# Pwr_Brd2.net
KiCad netlist of a schematic drawn in Altium Designer
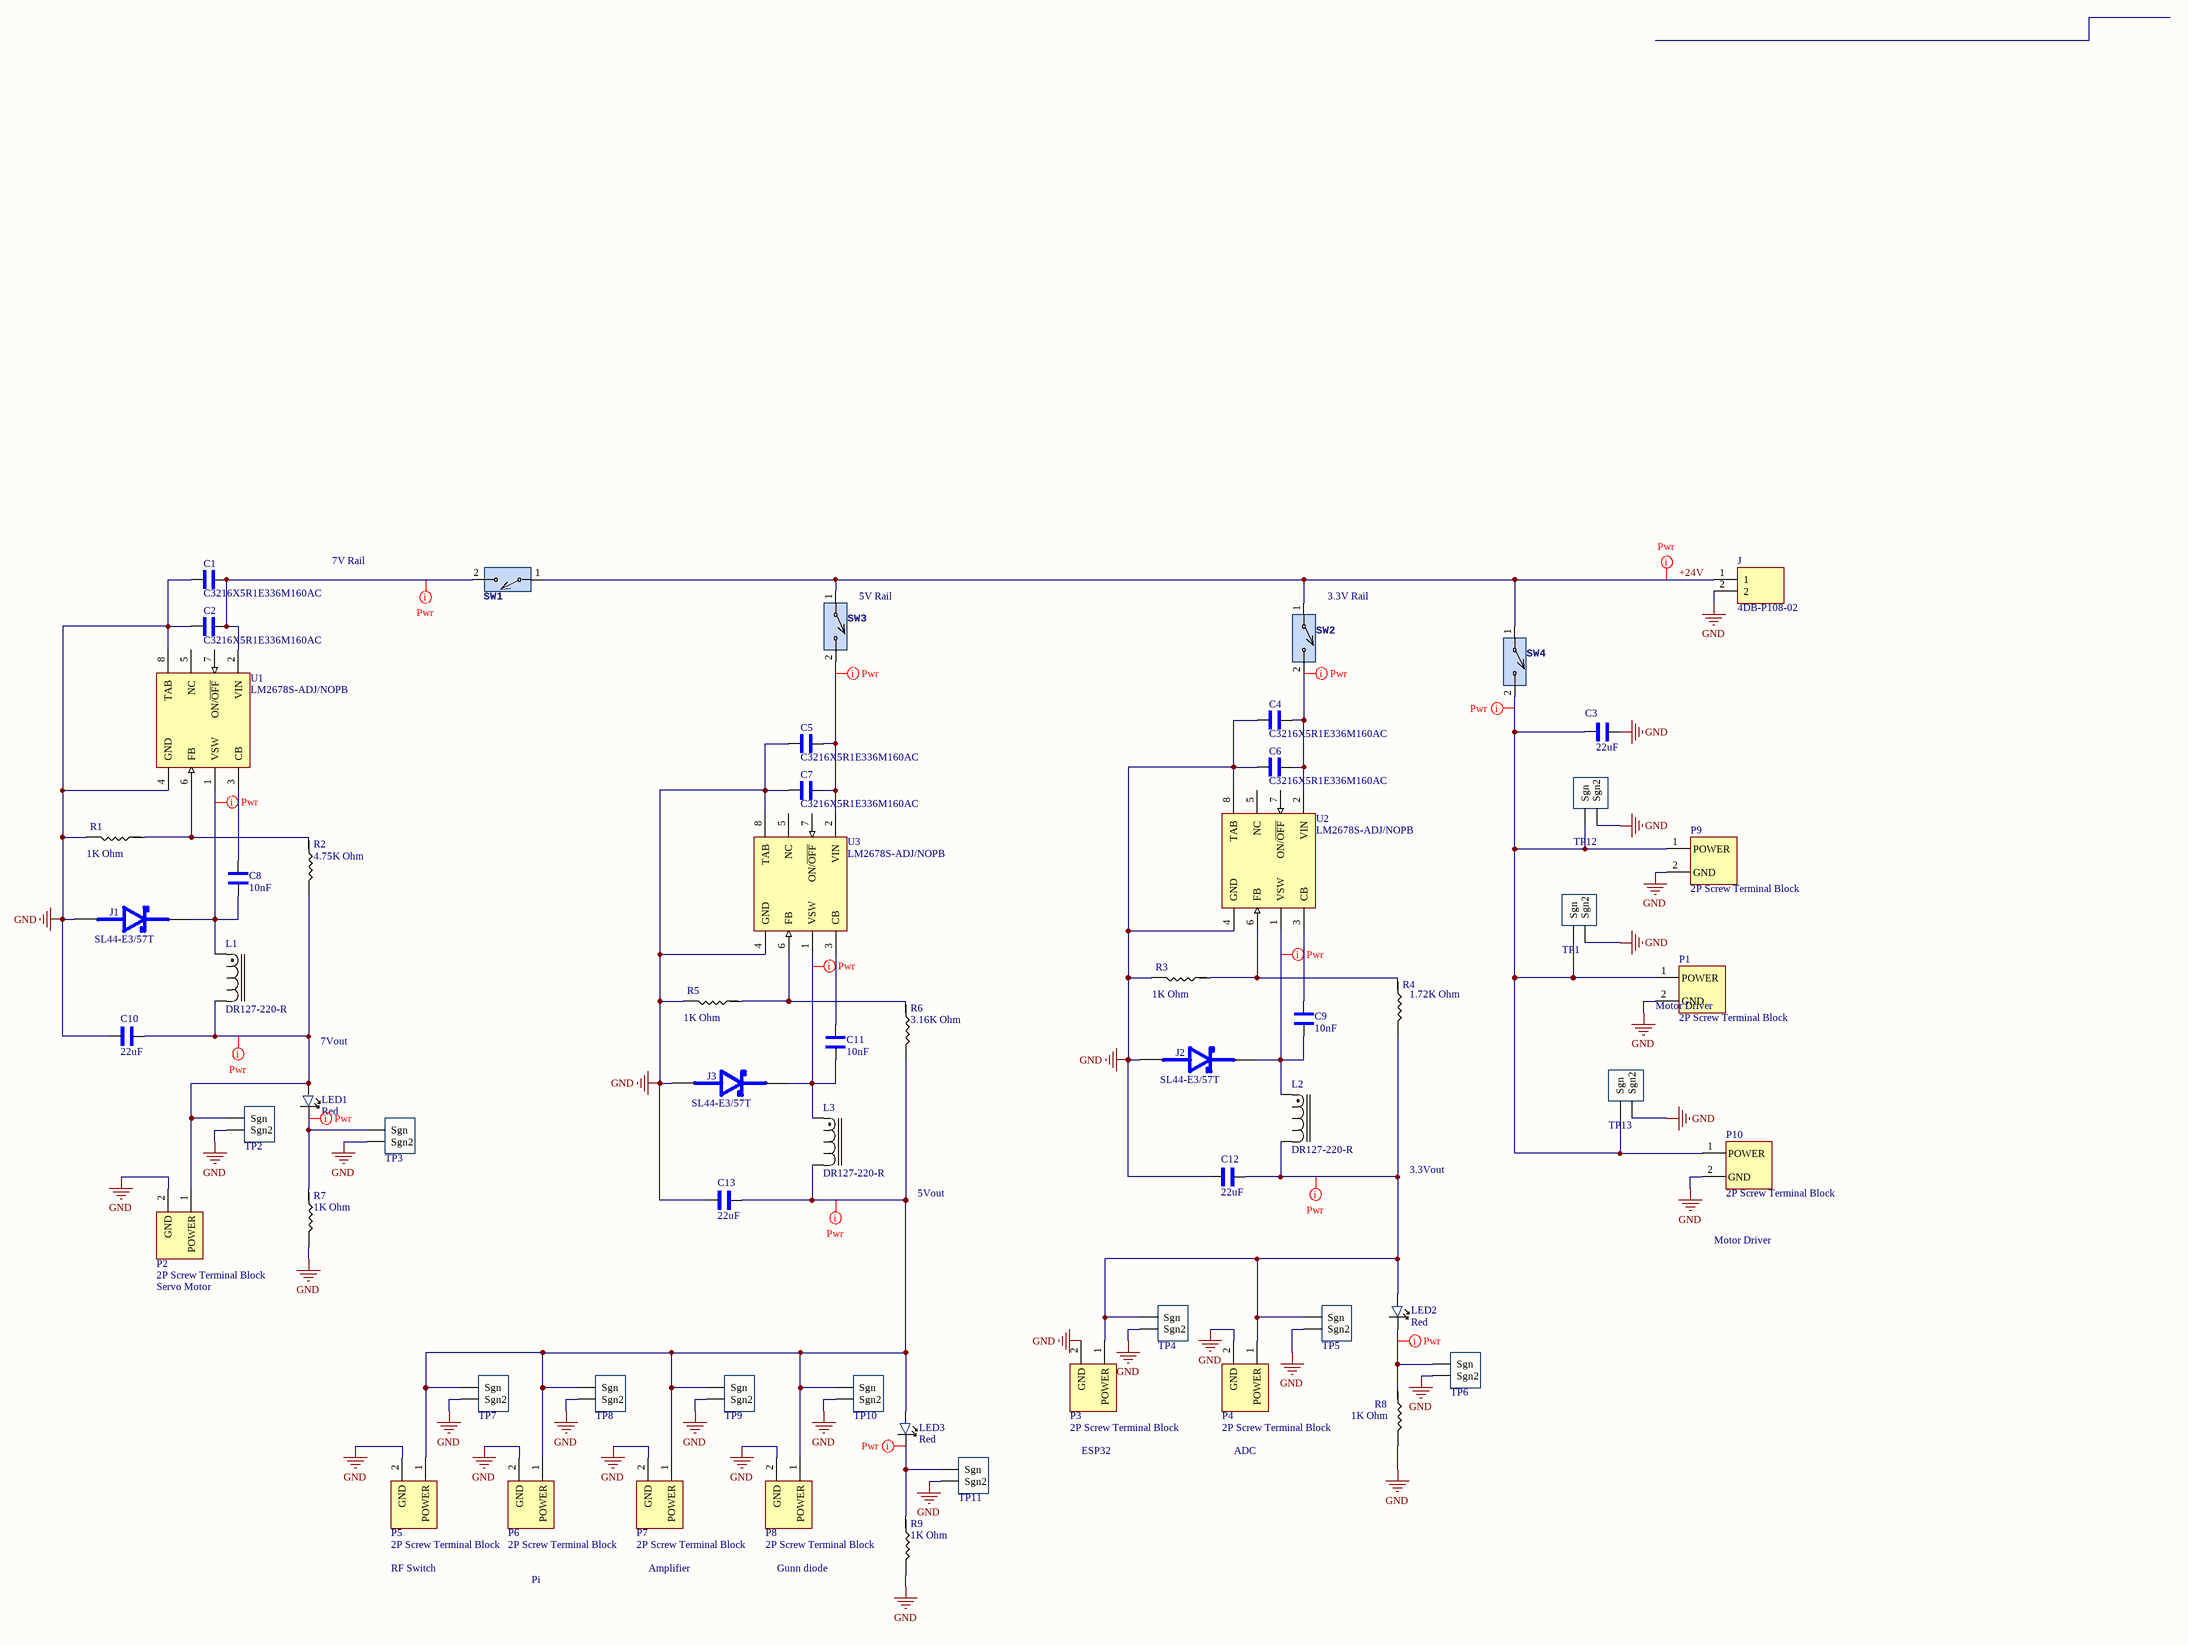
[diagram p0: Pwr_Brd2.SchDoc]

(export (version "E")
  (design (tool "Eeschema 10.0.6"))
  (components
    (comp (ref "C1")
      (value "C3216X5R1E336M160AC")
      (footprint "CAPC3216X180N")
      (description "Cap Ceramic 33uF 25V X5R 20% Pad SMD 1206 85Â°C Low ESR T/R")
      (fields (field (name "MF") "TDK Electronics"))
      (libsource (lib "C3216X5R1E336M160AC") (part "C3216X5R1E336M160AC"))
    )
    (comp (ref "C2")
      (value "C3216X5R1E336M160AC")
      (footprint "CAPC3216X180N")
      (description "Cap Ceramic 33uF 25V X5R 20% Pad SMD 1206 85Â°C Low ESR T/R")
      (fields (field (name "MF") "TDK Electronics"))
      (libsource (lib "C3216X5R1E336M160AC") (part "C3216X5R1E336M160AC"))
    )
    (comp (ref "C3")
      (value "22uF")
      (footprint "1206_Passive_Capacitor")
      (description "22uF ±10% 25V X5R 1206 Multilayer Ceramic Capacitors MLCC - SMD/SMT RoHS")
      (fields (field (name "MFR PART #") "CL31A226KAHNNNE") (field (name "LCSC PART#") "C12891"))
      (libsource (lib "Capstone_Stock_Library") (part "C_22uF_1206"))
    )
    (comp (ref "C4")
      (value "C3216X5R1E336M160AC")
      (footprint "CAPC3216X180N")
      (description "Cap Ceramic 33uF 25V X5R 20% Pad SMD 1206 85Â°C Low ESR T/R")
      (fields (field (name "MF") "TDK Electronics"))
      (libsource (lib "C3216X5R1E336M160AC") (part "C3216X5R1E336M160AC"))
    )
    (comp (ref "C5")
      (value "C3216X5R1E336M160AC")
      (footprint "CAPC3216X180N")
      (description "Cap Ceramic 33uF 25V X5R 20% Pad SMD 1206 85Â°C Low ESR T/R")
      (fields (field (name "MF") "TDK Electronics"))
      (libsource (lib "C3216X5R1E336M160AC") (part "C3216X5R1E336M160AC"))
    )
    (comp (ref "C6")
      (value "C3216X5R1E336M160AC")
      (footprint "CAPC3216X180N")
      (description "Cap Ceramic 33uF 25V X5R 20% Pad SMD 1206 85Â°C Low ESR T/R")
      (fields (field (name "MF") "TDK Electronics"))
      (libsource (lib "C3216X5R1E336M160AC") (part "C3216X5R1E336M160AC"))
    )
    (comp (ref "C7")
      (value "C3216X5R1E336M160AC")
      (footprint "CAPC3216X180N")
      (description "Cap Ceramic 33uF 25V X5R 20% Pad SMD 1206 85Â°C Low ESR T/R")
      (fields (field (name "MF") "TDK Electronics"))
      (libsource (lib "C3216X5R1E336M160AC") (part "C3216X5R1E336M160AC"))
    )
    (comp (ref "C8")
      (value "10nF")
      (footprint "1206_Passive_Capacitor")
      (description "10nF 50V X7R ±10% 1206 Multilayer Ceramic Capacitors MLCC - SMD/SMT ROHS")
      (fields (field (name "MFR PART #") "CL31B105KBHNNNE") (field (name "LCSC PART#") "C1848"))
      (libsource (lib "Capstone_Stock_Library") (part "C_10nF_1206"))
    )
    (comp (ref "C9")
      (value "10nF")
      (footprint "1206_Passive_Capacitor")
      (description "10nF 50V X7R ±10% 1206 Multilayer Ceramic Capacitors MLCC - SMD/SMT ROHS")
      (fields (field (name "MFR PART #") "CL31B105KBHNNNE") (field (name "LCSC PART#") "C1848"))
      (libsource (lib "Capstone_Stock_Library") (part "C_10nF_1206"))
    )
    (comp (ref "C10")
      (value "22uF")
      (footprint "1206_Passive_Capacitor")
      (description "22uF ±10% 25V X5R 1206 Multilayer Ceramic Capacitors MLCC - SMD/SMT RoHS")
      (fields (field (name "MFR PART #") "CL31A226KAHNNNE") (field (name "LCSC PART#") "C12891"))
      (libsource (lib "Capstone_Stock_Library") (part "C_22uF_1206"))
    )
    (comp (ref "C11")
      (value "10nF")
      (footprint "1206_Passive_Capacitor")
      (description "10nF 50V X7R ±10% 1206 Multilayer Ceramic Capacitors MLCC - SMD/SMT ROHS")
      (fields (field (name "MFR PART #") "CL31B105KBHNNNE") (field (name "LCSC PART#") "C1848"))
      (libsource (lib "Capstone_Stock_Library") (part "C_10nF_1206"))
    )
    (comp (ref "C12")
      (value "22uF")
      (footprint "1206_Passive_Capacitor")
      (description "22uF ±10% 25V X5R 1206 Multilayer Ceramic Capacitors MLCC - SMD/SMT RoHS")
      (fields (field (name "MFR PART #") "CL31A226KAHNNNE") (field (name "LCSC PART#") "C12891"))
      (libsource (lib "Capstone_Stock_Library") (part "C_22uF_1206"))
    )
    (comp (ref "C13")
      (value "22uF")
      (footprint "1206_Passive_Capacitor")
      (description "22uF ±10% 25V X5R 1206 Multilayer Ceramic Capacitors MLCC - SMD/SMT RoHS")
      (fields (field (name "MFR PART #") "CL31A226KAHNNNE") (field (name "LCSC PART#") "C12891"))
      (libsource (lib "Capstone_Stock_Library") (part "C_22uF_1206"))
    )
    (comp (ref "J")
      (value "4DB-P108-02")
      (footprint "TE_2-1437667-4")
      (description "Conn; Term Strip; Barrier; 2Pole; 8.26mmPitch; SnglRow; 22-12; Series 4DB; 20A; 150V")
      (fields (field (name "MF") "TE Connectivity"))
      (libsource (lib "4DB-P108-02") (part "4DB-P108-02"))
    )
    (comp (ref "J1")
      (value "SL44-E3/57T")
      (footprint "DIOM7959X262N")
      (description "Diode Schottky 40 V 4A Surface Mount DO-214AB (SMC)")
      (fields (field (name "MF") "Vishay Semiconductor"))
      (libsource (lib "SL44-E3_57T") (part "SL44-E3/57T"))
    )
    (comp (ref "J2")
      (value "SL44-E3/57T")
      (footprint "DIOM7959X262N")
      (description "Diode Schottky 40 V 4A Surface Mount DO-214AB (SMC)")
      (fields (field (name "MF") "Vishay Semiconductor"))
      (libsource (lib "SL44-E3_57T") (part "SL44-E3/57T"))
    )
    (comp (ref "J3")
      (value "SL44-E3/57T")
      (footprint "DIOM7959X262N")
      (description "Diode Schottky 40 V 4A Surface Mount DO-214AB (SMC)")
      (fields (field (name "MF") "Vishay Semiconductor"))
      (libsource (lib "SL44-E3_57T") (part "SL44-E3/57T"))
    )
    (comp (ref "L1")
      (value "DR127-220-R")
      (footprint "DR127")
      (description "Description")
      (fields (field (name "COPYRIGHT") "Copyright (C) 2025 Ultra Librarian. All rights reserved."))
      (libsource (lib "DR127-220-R") (part "DR127-220-R"))
    )
    (comp (ref "L2")
      (value "DR127-220-R")
      (footprint "DR127")
      (description "Description")
      (fields (field (name "COPYRIGHT") "Copyright (C) 2025 Ultra Librarian. All rights reserved."))
      (libsource (lib "DR127-220-R") (part "DR127-220-R"))
    )
    (comp (ref "L3")
      (value "DR127-220-R")
      (footprint "DR127")
      (description "Description")
      (fields (field (name "COPYRIGHT") "Copyright (C) 2025 Ultra Librarian. All rights reserved."))
      (libsource (lib "DR127-220-R") (part "DR127-220-R"))
    )
    (comp (ref "LED1")
      (value "Red")
      (footprint "LED_1206")
      (description "Red 621~631nm 1206 Light Emitting Diodes (LED) RoHS")
      (fields (field (name "MFR PART #") "15-21/R6C-FQ1R1B/2T") (field (name "LCSC PART#") "C93133"))
      (libsource (lib "Capstone_Stock_Library") (part "LED_RED_1206"))
    )
    (comp (ref "LED2")
      (value "Red")
      (footprint "LED_1206")
      (description "Red 621~631nm 1206 Light Emitting Diodes (LED) RoHS")
      (fields (field (name "MFR PART #") "15-21/R6C-FQ1R1B/2T") (field (name "LCSC PART#") "C93133"))
      (libsource (lib "Capstone_Stock_Library") (part "LED_RED_1206"))
    )
    (comp (ref "LED3")
      (value "Red")
      (footprint "LED_1206")
      (description "Red 621~631nm 1206 Light Emitting Diodes (LED) RoHS")
      (fields (field (name "MFR PART #") "15-21/R6C-FQ1R1B/2T") (field (name "LCSC PART#") "C93133"))
      (libsource (lib "Capstone_Stock_Library") (part "LED_RED_1206"))
    )
    (comp (ref "P1")
      (value "2P Screw Terminal Block")
      (footprint "P_Terminal block 3.5mm-pitch")
      (description "Green Straight pin 3.5mm  pitch; P=3.5mm  Screw terminal ROHS")
      (fields (field (name "MFR PART #") "KF350-3.5-2P") (field (name "MANUFACTURER") "Cixi Kefa Elec"))
      (libsource (lib "Capstone_Stock_Library") (part "P_Terminal block"))
    )
    (comp (ref "P2")
      (value "2P Screw Terminal Block")
      (footprint "P_Terminal block 3.5mm-pitch")
      (description "Green Straight pin 3.5mm  pitch; P=3.5mm  Screw terminal ROHS")
      (fields (field (name "MFR PART #") "KF350-3.5-2P") (field (name "MANUFACTURER") "Cixi Kefa Elec"))
      (libsource (lib "") (part "P_Terminal block_1"))
    )
    (comp (ref "P3")
      (value "2P Screw Terminal Block")
      (footprint "P_Terminal block 3.5mm-pitch")
      (description "Green Straight pin 3.5mm  pitch; P=3.5mm  Screw terminal ROHS")
      (fields (field (name "MFR PART #") "KF350-3.5-2P") (field (name "MANUFACTURER") "Cixi Kefa Elec"))
      (libsource (lib "") (part "P_Terminal block_1"))
    )
    (comp (ref "P4")
      (value "2P Screw Terminal Block")
      (footprint "P_Terminal block 3.5mm-pitch")
      (description "Green Straight pin 3.5mm  pitch; P=3.5mm  Screw terminal ROHS")
      (fields (field (name "MFR PART #") "KF350-3.5-2P") (field (name "MANUFACTURER") "Cixi Kefa Elec"))
      (libsource (lib "") (part "P_Terminal block_1"))
    )
    (comp (ref "P5")
      (value "2P Screw Terminal Block")
      (footprint "P_Terminal block 3.5mm-pitch")
      (description "Green Straight pin 3.5mm  pitch; P=3.5mm  Screw terminal ROHS")
      (fields (field (name "MFR PART #") "KF350-3.5-2P") (field (name "MANUFACTURER") "Cixi Kefa Elec"))
      (libsource (lib "") (part "P_Terminal block_1"))
    )
    (comp (ref "P6")
      (value "2P Screw Terminal Block")
      (footprint "P_Terminal block 3.5mm-pitch")
      (description "Green Straight pin 3.5mm  pitch; P=3.5mm  Screw terminal ROHS")
      (fields (field (name "MFR PART #") "KF350-3.5-2P") (field (name "MANUFACTURER") "Cixi Kefa Elec"))
      (libsource (lib "") (part "P_Terminal block_1"))
    )
    (comp (ref "P7")
      (value "2P Screw Terminal Block")
      (footprint "P_Terminal block 3.5mm-pitch")
      (description "Green Straight pin 3.5mm  pitch; P=3.5mm  Screw terminal ROHS")
      (fields (field (name "MFR PART #") "KF350-3.5-2P") (field (name "MANUFACTURER") "Cixi Kefa Elec"))
      (libsource (lib "") (part "P_Terminal block_1"))
    )
    (comp (ref "P8")
      (value "2P Screw Terminal Block")
      (footprint "P_Terminal block 3.5mm-pitch")
      (description "Green Straight pin 3.5mm  pitch; P=3.5mm  Screw terminal ROHS")
      (fields (field (name "MFR PART #") "KF350-3.5-2P") (field (name "MANUFACTURER") "Cixi Kefa Elec"))
      (libsource (lib "") (part "P_Terminal block_1"))
    )
    (comp (ref "P9")
      (value "2P Screw Terminal Block")
      (footprint "P_Terminal block 3.5mm-pitch")
      (description "Green Straight pin 3.5mm  pitch; P=3.5mm  Screw terminal ROHS")
      (fields (field (name "MFR PART #") "KF350-3.5-2P") (field (name "MANUFACTURER") "Cixi Kefa Elec"))
      (libsource (lib "Capstone_Stock_Library") (part "P_Terminal block"))
    )
    (comp (ref "P10")
      (value "2P Screw Terminal Block")
      (footprint "P_Terminal block 3.5mm-pitch")
      (description "Green Straight pin 3.5mm  pitch; P=3.5mm  Screw terminal ROHS")
      (fields (field (name "MFR PART #") "KF350-3.5-2P") (field (name "MANUFACTURER") "Cixi Kefa Elec"))
      (libsource (lib "Capstone_Stock_Library") (part "P_Terminal block"))
    )
    (comp (ref "R1")
      (value "1K Ohm")
      (footprint "1206_Passive_Resitor")
      (description "CHIP RESISTOR - SURFACE MOUNT 1KOHMS ±1% 1/4W 1206 ROHS")
      (fields (field (name "MFR PART #") "RNCP1206FTD1K00CT") (field (name "LCSC PART#") "C4410"))
      (libsource (lib "Capstone_Stock_Library") (part "R_1K_1206"))
    )
    (comp (ref "R2")
      (value "4.75K Ohm")
      (footprint "1206_Passive_Resitor")
      (description "CHIP RESISTOR - SURFACE MOUNT 1KOHMS ±1% 1/4W 1206 ROHS")
      (fields (field (name "MFR PART #") "RNCP1206FTD1K00CT") (field (name "LCSC PART#") "C4410"))
      (libsource (lib "Capstone_Stock_Library") (part "R_1K_1206"))
    )
    (comp (ref "R3")
      (value "1K Ohm")
      (footprint "1206_Passive_Resitor")
      (description "CHIP RESISTOR - SURFACE MOUNT 1KOHMS ±1% 1/4W 1206 ROHS")
      (fields (field (name "MFR PART #") "RNCP1206FTD1K00CT") (field (name "LCSC PART#") "C4410"))
      (libsource (lib "Capstone_Stock_Library") (part "R_1K_1206"))
    )
    (comp (ref "R4")
      (value "1.72K Ohm")
      (footprint "1206_Passive_Resitor")
      (description "CHIP RESISTOR - SURFACE MOUNT 1KOHMS ±1% 1/4W 1206 ROHS")
      (fields (field (name "MFR PART #") "RNCP1206FTD1K00CT") (field (name "LCSC PART#") "C4410"))
      (libsource (lib "Capstone_Stock_Library") (part "R_1K_1206"))
    )
    (comp (ref "R5")
      (value "1K Ohm")
      (footprint "1206_Passive_Resitor")
      (description "CHIP RESISTOR - SURFACE MOUNT 1KOHMS ±1% 1/4W 1206 ROHS")
      (fields (field (name "MFR PART #") "RNCP1206FTD1K00CT") (field (name "LCSC PART#") "C4410"))
      (libsource (lib "Capstone_Stock_Library") (part "R_1K_1206"))
    )
    (comp (ref "R6")
      (value "3.16K Ohm")
      (footprint "1206_Passive_Resitor")
      (description "CHIP RESISTOR - SURFACE MOUNT 1KOHMS ±1% 1/4W 1206 ROHS")
      (fields (field (name "MFR PART #") "RNCP1206FTD1K00CT") (field (name "LCSC PART#") "C4410"))
      (libsource (lib "Capstone_Stock_Library") (part "R_1K_1206"))
    )
    (comp (ref "R7")
      (value "1K Ohm")
      (footprint "1206_Passive_Resitor")
      (description "CHIP RESISTOR - SURFACE MOUNT 1KOHMS ±1% 1/4W 1206 ROHS")
      (fields (field (name "MFR PART #") "RNCP1206FTD1K00CT") (field (name "LCSC PART#") "C4410"))
      (libsource (lib "Capstone_Stock_Library") (part "R_1K_1206"))
    )
    (comp (ref "R8")
      (value "1K Ohm")
      (footprint "1206_Passive_Resitor")
      (description "CHIP RESISTOR - SURFACE MOUNT 1KOHMS ±1% 1/4W 1206 ROHS")
      (fields (field (name "MFR PART #") "RNCP1206FTD1K00CT") (field (name "LCSC PART#") "C4410"))
      (libsource (lib "Capstone_Stock_Library") (part "R_1K_1206"))
    )
    (comp (ref "R9")
      (value "1K Ohm")
      (footprint "1206_Passive_Resitor")
      (description "CHIP RESISTOR - SURFACE MOUNT 1KOHMS ±1% 1/4W 1206 ROHS")
      (fields (field (name "MFR PART #") "RNCP1206FTD1K00CT") (field (name "LCSC PART#") "C4410"))
      (libsource (lib "Capstone_Stock_Library") (part "R_1K_1206"))
    )
    (comp (ref "SW1")
      (value "SW_2Pin_100mil_Switch")
      (footprint "2Pin-Header-Conn")
      (description "2Pin Header")
      (fields (field (name "LCSC PART#") "C124375"))
      (libsource (lib "") (part "SW_2Pin_100mil_Switch_1"))
    )
    (comp (ref "SW2")
      (value "SW_2Pin_100mil_Switch")
      (footprint "2Pin-Header-Conn")
      (description "2Pin Header")
      (fields (field (name "LCSC PART#") "C124375"))
      (libsource (lib "Capstone_Stock_Library") (part "SW_2Pin_100mil_Switch"))
    )
    (comp (ref "SW3")
      (value "SW_2Pin_100mil_Switch")
      (footprint "2Pin-Header-Conn")
      (description "2Pin Header")
      (fields (field (name "LCSC PART#") "C124375"))
      (libsource (lib "Capstone_Stock_Library") (part "SW_2Pin_100mil_Switch"))
    )
    (comp (ref "SW4")
      (value "SW_2Pin_100mil_Switch")
      (footprint "2Pin-Header-Conn")
      (description "2Pin Header")
      (fields (field (name "LCSC PART#") "C124375"))
      (libsource (lib "Capstone_Stock_Library") (part "SW_2Pin_100mil_Switch"))
    )
    (comp (ref "TP1")
      (value "10x Probe TP")
      (footprint "TP_Diff_Probe")
      (description "Test Point 300 mil centers")
      (libsource (lib "") (part "TP_Diff_Probe_1"))
    )
    (comp (ref "TP2")
      (value "10x Probe TP")
      (footprint "TP_Diff_Probe")
      (description "Test Point 300 mil centers")
      (libsource (lib "Capstone_Stock_Library") (part "TP_Diff_Probe"))
    )
    (comp (ref "TP3")
      (value "10x Probe TP")
      (footprint "TP_Diff_Probe")
      (description "Test Point 300 mil centers")
      (libsource (lib "Capstone_Stock_Library") (part "TP_Diff_Probe"))
    )
    (comp (ref "TP4")
      (value "10x Probe TP")
      (footprint "TP_Diff_Probe")
      (description "Test Point 300 mil centers")
      (libsource (lib "Capstone_Stock_Library") (part "TP_Diff_Probe"))
    )
    (comp (ref "TP5")
      (value "10x Probe TP")
      (footprint "TP_Diff_Probe")
      (description "Test Point 300 mil centers")
      (libsource (lib "Capstone_Stock_Library") (part "TP_Diff_Probe"))
    )
    (comp (ref "TP6")
      (value "10x Probe TP")
      (footprint "TP_Diff_Probe")
      (description "Test Point 300 mil centers")
      (libsource (lib "Capstone_Stock_Library") (part "TP_Diff_Probe"))
    )
    (comp (ref "TP7")
      (value "10x Probe TP")
      (footprint "TP_Diff_Probe")
      (description "Test Point 300 mil centers")
      (libsource (lib "Capstone_Stock_Library") (part "TP_Diff_Probe"))
    )
    (comp (ref "TP8")
      (value "10x Probe TP")
      (footprint "TP_Diff_Probe")
      (description "Test Point 300 mil centers")
      (libsource (lib "Capstone_Stock_Library") (part "TP_Diff_Probe"))
    )
    (comp (ref "TP9")
      (value "10x Probe TP")
      (footprint "TP_Diff_Probe")
      (description "Test Point 300 mil centers")
      (libsource (lib "Capstone_Stock_Library") (part "TP_Diff_Probe"))
    )
    (comp (ref "TP10")
      (value "10x Probe TP")
      (footprint "TP_Diff_Probe")
      (description "Test Point 300 mil centers")
      (libsource (lib "Capstone_Stock_Library") (part "TP_Diff_Probe"))
    )
    (comp (ref "TP11")
      (value "10x Probe TP")
      (footprint "TP_Diff_Probe")
      (description "Test Point 300 mil centers")
      (libsource (lib "Capstone_Stock_Library") (part "TP_Diff_Probe"))
    )
    (comp (ref "TP12")
      (value "10x Probe TP")
      (footprint "TP_Diff_Probe")
      (description "Test Point 300 mil centers")
      (libsource (lib "") (part "TP_Diff_Probe_1"))
    )
    (comp (ref "TP13")
      (value "10x Probe TP")
      (footprint "TP_Diff_Probe")
      (description "Test Point 300 mil centers")
      (libsource (lib "") (part "TP_Diff_Probe_1"))
    )
    (comp (ref "U1")
      (value "LM2678S-ADJ/NOPB")
      (footprint "KTW0007B_N")
      (description "SIMPLE SWITCHER® High Efficiency 5A Step-Down Voltage Regulator, 7-pin TO-263, Pb-Free")
      (fields (field (name "MANUFACTURER") "Texas Instruments"))
      (libsource (lib "Altium Content Vault") (part "PM-REG-LM2678S"))
    )
    (comp (ref "U2")
      (value "LM2678S-ADJ/NOPB")
      (footprint "KTW0007B_N")
      (description "SIMPLE SWITCHER® High Efficiency 5A Step-Down Voltage Regulator, 7-pin TO-263, Pb-Free")
      (fields (field (name "MANUFACTURER") "Texas Instruments"))
      (libsource (lib "Altium Content Vault") (part "PM-REG-LM2678S"))
    )
    (comp (ref "U3")
      (value "LM2678S-ADJ/NOPB")
      (footprint "KTW0007B_N")
      (description "SIMPLE SWITCHER® High Efficiency 5A Step-Down Voltage Regulator, 7-pin TO-263, Pb-Free")
      (fields (field (name "MANUFACTURER") "Texas Instruments"))
      (libsource (lib "Altium Content Vault") (part "PM-REG-LM2678S"))
    )
  )
  (nets
    (net (code "1") (name "/+24V") (class "Default")
      (node (ref "J") (pin "1") (pinfunction "1_1") (pintype "passive"))
      (node (ref "SW1") (pin "1") (pinfunction "1_1") (pintype "passive"))
      (node (ref "SW2") (pin "1") (pinfunction "1_1") (pintype "passive"))
      (node (ref "SW3") (pin "1") (pinfunction "1_1") (pintype "passive"))
      (node (ref "SW4") (pin "1") (pinfunction "1_1") (pintype "passive"))
    )
    (net (code "2") (name "GND") (class "Default")
      (node (ref "C1") (pin "1") (pinfunction "1_1") (pintype "passive"))
      (node (ref "C10") (pin "1") (pinfunction "1_1") (pintype "passive"))
      (node (ref "C12") (pin "1") (pinfunction "1_1") (pintype "passive"))
      (node (ref "C13") (pin "1") (pinfunction "1_1") (pintype "passive"))
      (node (ref "C2") (pin "1") (pinfunction "1_1") (pintype "passive"))
      (node (ref "C3") (pin "2") (pinfunction "2_2") (pintype "passive"))
      (node (ref "C4") (pin "1") (pinfunction "1_1") (pintype "passive"))
      (node (ref "C5") (pin "1") (pinfunction "1_1") (pintype "passive"))
      (node (ref "C6") (pin "1") (pinfunction "1_1") (pintype "passive"))
      (node (ref "C7") (pin "1") (pinfunction "1_1") (pintype "passive"))
      (node (ref "J") (pin "2") (pinfunction "2_2") (pintype "passive"))
      (node (ref "J1") (pin "A") (pinfunction "A_A") (pintype "passive"))
      (node (ref "J2") (pin "A") (pinfunction "A_A") (pintype "passive"))
      (node (ref "J3") (pin "A") (pinfunction "A_A") (pintype "passive"))
      (node (ref "P1") (pin "2") (pinfunction "GND_2") (pintype "passive"))
      (node (ref "P10") (pin "2") (pinfunction "GND_2") (pintype "passive"))
      (node (ref "P2") (pin "2") (pinfunction "GND_2") (pintype "passive"))
      (node (ref "P3") (pin "2") (pinfunction "GND_2") (pintype "passive"))
      (node (ref "P4") (pin "2") (pinfunction "GND_2") (pintype "passive"))
      (node (ref "P5") (pin "2") (pinfunction "GND_2") (pintype "passive"))
      (node (ref "P6") (pin "2") (pinfunction "GND_2") (pintype "passive"))
      (node (ref "P7") (pin "2") (pinfunction "GND_2") (pintype "passive"))
      (node (ref "P8") (pin "2") (pinfunction "GND_2") (pintype "passive"))
      (node (ref "P9") (pin "2") (pinfunction "GND_2") (pintype "passive"))
      (node (ref "R1") (pin "2") (pinfunction "2_2") (pintype "passive"))
      (node (ref "R3") (pin "2") (pinfunction "2_2") (pintype "passive"))
      (node (ref "R5") (pin "2") (pinfunction "2_2") (pintype "passive"))
      (node (ref "R7") (pin "2") (pinfunction "2_2") (pintype "passive"))
      (node (ref "R8") (pin "2") (pinfunction "2_2") (pintype "passive"))
      (node (ref "R9") (pin "2") (pinfunction "2_2") (pintype "passive"))
      (node (ref "TP1") (pin "2") (pinfunction "Sgn2_2") (pintype "passive"))
      (node (ref "TP10") (pin "2") (pinfunction "Sgn2_2") (pintype "passive"))
      (node (ref "TP11") (pin "2") (pinfunction "Sgn2_2") (pintype "passive"))
      (node (ref "TP12") (pin "2") (pinfunction "Sgn2_2") (pintype "passive"))
      (node (ref "TP13") (pin "2") (pinfunction "Sgn2_2") (pintype "passive"))
      (node (ref "TP2") (pin "2") (pinfunction "Sgn2_2") (pintype "passive"))
      (node (ref "TP3") (pin "2") (pinfunction "Sgn2_2") (pintype "passive"))
      (node (ref "TP4") (pin "2") (pinfunction "Sgn2_2") (pintype "passive"))
      (node (ref "TP5") (pin "2") (pinfunction "Sgn2_2") (pintype "passive"))
      (node (ref "TP6") (pin "2") (pinfunction "Sgn2_2") (pintype "passive"))
      (node (ref "TP7") (pin "2") (pinfunction "Sgn2_2") (pintype "passive"))
      (node (ref "TP8") (pin "2") (pinfunction "Sgn2_2") (pintype "passive"))
      (node (ref "TP9") (pin "2") (pinfunction "Sgn2_2") (pintype "passive"))
      (node (ref "U1") (pin "4") (pinfunction "GND_4") (pintype "power_in"))
      (node (ref "U1") (pin "8") (pinfunction "TAB_8") (pintype "power_in"))
      (node (ref "U2") (pin "4") (pinfunction "GND_4") (pintype "power_in"))
      (node (ref "U2") (pin "8") (pinfunction "TAB_8") (pintype "power_in"))
      (node (ref "U3") (pin "4") (pinfunction "GND_4") (pintype "power_in"))
      (node (ref "U3") (pin "8") (pinfunction "TAB_8") (pintype "power_in"))
    )
    (net (code "3") (name "Net-(P1-POWER)") (class "Default")
      (node (ref "C3") (pin "1") (pinfunction "1_1") (pintype "passive"))
      (node (ref "P1") (pin "1") (pinfunction "POWER_1") (pintype "passive"))
      (node (ref "P10") (pin "1") (pinfunction "POWER_1") (pintype "passive"))
      (node (ref "P9") (pin "1") (pinfunction "POWER_1") (pintype "passive"))
      (node (ref "SW4") (pin "2") (pinfunction "2_2") (pintype "passive"))
      (node (ref "TP1") (pin "1") (pinfunction "Sgn_1") (pintype "passive"))
      (node (ref "TP12") (pin "1") (pinfunction "Sgn_1") (pintype "passive"))
      (node (ref "TP13") (pin "1") (pinfunction "Sgn_1") (pintype "passive"))
    )
    (net (code "4") (name "Net-(P2-POWER)") (class "Default")
      (node (ref "C10") (pin "2") (pinfunction "2_2") (pintype "passive"))
      (node (ref "L1") (pin "2") (pinfunction "2_2") (pintype "passive"))
      (node (ref "LED1") (pin "1") (pinfunction "1_1") (pintype "passive"))
      (node (ref "P2") (pin "1") (pinfunction "POWER_1") (pintype "passive"))
      (node (ref "R2") (pin "2") (pinfunction "2_2") (pintype "passive"))
      (node (ref "TP2") (pin "1") (pinfunction "Sgn_1") (pintype "passive"))
    )
    (net (code "5") (name "Net-(P3-POWER)") (class "Default")
      (node (ref "C12") (pin "2") (pinfunction "2_2") (pintype "passive"))
      (node (ref "L2") (pin "2") (pinfunction "2_2") (pintype "passive"))
      (node (ref "LED2") (pin "1") (pinfunction "1_1") (pintype "passive"))
      (node (ref "P3") (pin "1") (pinfunction "POWER_1") (pintype "passive"))
      (node (ref "P4") (pin "1") (pinfunction "POWER_1") (pintype "passive"))
      (node (ref "R4") (pin "2") (pinfunction "2_2") (pintype "passive"))
      (node (ref "TP4") (pin "1") (pinfunction "Sgn_1") (pintype "passive"))
      (node (ref "TP5") (pin "1") (pinfunction "Sgn_1") (pintype "passive"))
    )
    (net (code "6") (name "Net-(P5-POWER)") (class "Default")
      (node (ref "C13") (pin "2") (pinfunction "2_2") (pintype "passive"))
      (node (ref "L3") (pin "2") (pinfunction "2_2") (pintype "passive"))
      (node (ref "LED3") (pin "1") (pinfunction "1_1") (pintype "passive"))
      (node (ref "P5") (pin "1") (pinfunction "POWER_1") (pintype "passive"))
      (node (ref "P6") (pin "1") (pinfunction "POWER_1") (pintype "passive"))
      (node (ref "P7") (pin "1") (pinfunction "POWER_1") (pintype "passive"))
      (node (ref "P8") (pin "1") (pinfunction "POWER_1") (pintype "passive"))
      (node (ref "R6") (pin "2") (pinfunction "2_2") (pintype "passive"))
      (node (ref "TP10") (pin "1") (pinfunction "Sgn_1") (pintype "passive"))
      (node (ref "TP7") (pin "1") (pinfunction "Sgn_1") (pintype "passive"))
      (node (ref "TP8") (pin "1") (pinfunction "Sgn_1") (pintype "passive"))
      (node (ref "TP9") (pin "1") (pinfunction "Sgn_1") (pintype "passive"))
    )
    (net (code "7") (name "Net-(TP3-Sgn)") (class "Default")
      (node (ref "LED1") (pin "2") (pinfunction "2_2") (pintype "passive"))
      (node (ref "R7") (pin "1") (pinfunction "1_1") (pintype "passive"))
      (node (ref "TP3") (pin "1") (pinfunction "Sgn_1") (pintype "passive"))
    )
    (net (code "8") (name "Net-(TP6-Sgn)") (class "Default")
      (node (ref "LED2") (pin "2") (pinfunction "2_2") (pintype "passive"))
      (node (ref "R8") (pin "1") (pinfunction "1_1") (pintype "passive"))
      (node (ref "TP6") (pin "1") (pinfunction "Sgn_1") (pintype "passive"))
    )
    (net (code "9") (name "Net-(TP11-Sgn)") (class "Default")
      (node (ref "LED3") (pin "2") (pinfunction "2_2") (pintype "passive"))
      (node (ref "R9") (pin "1") (pinfunction "1_1") (pintype "passive"))
      (node (ref "TP11") (pin "1") (pinfunction "Sgn_1") (pintype "passive"))
    )
    (net (code "10") (name "Net-(U1-CB)") (class "Default")
      (node (ref "C8") (pin "2") (pinfunction "2_2") (pintype "passive"))
      (node (ref "U1") (pin "3") (pinfunction "CB_3") (pintype "passive"))
    )
    (net (code "11") (name "Net-(U1-FB)") (class "Default")
      (node (ref "R1") (pin "1") (pinfunction "1_1") (pintype "passive"))
      (node (ref "R2") (pin "1") (pinfunction "1_1") (pintype "passive"))
      (node (ref "U1") (pin "6") (pinfunction "FB_6") (pintype "input"))
    )
    (net (code "12") (name "Net-(U1-VIN)") (class "Default")
      (node (ref "C1") (pin "2") (pinfunction "2_2") (pintype "passive"))
      (node (ref "C2") (pin "2") (pinfunction "2_2") (pintype "passive"))
      (node (ref "SW1") (pin "2") (pinfunction "2_2") (pintype "passive"))
      (node (ref "U1") (pin "2") (pinfunction "VIN_2") (pintype "power_in"))
    )
    (net (code "13") (name "Net-(U1-VSW)") (class "Default")
      (node (ref "C8") (pin "1") (pinfunction "1_1") (pintype "passive"))
      (node (ref "J1") (pin "C") (pinfunction "C_C") (pintype "passive"))
      (node (ref "L1") (pin "1") (pinfunction "1_1") (pintype "passive"))
      (node (ref "U1") (pin "1") (pinfunction "VSW_1") (pintype "power_in"))
    )
    (net (code "14") (name "Net-(U2-CB)") (class "Default")
      (node (ref "C9") (pin "2") (pinfunction "2_2") (pintype "passive"))
      (node (ref "U2") (pin "3") (pinfunction "CB_3") (pintype "passive"))
    )
    (net (code "15") (name "Net-(U2-FB)") (class "Default")
      (node (ref "R3") (pin "1") (pinfunction "1_1") (pintype "passive"))
      (node (ref "R4") (pin "1") (pinfunction "1_1") (pintype "passive"))
      (node (ref "U2") (pin "6") (pinfunction "FB_6") (pintype "input"))
    )
    (net (code "16") (name "Net-(U2-VIN)") (class "Default")
      (node (ref "C4") (pin "2") (pinfunction "2_2") (pintype "passive"))
      (node (ref "C6") (pin "2") (pinfunction "2_2") (pintype "passive"))
      (node (ref "SW2") (pin "2") (pinfunction "2_2") (pintype "passive"))
      (node (ref "U2") (pin "2") (pinfunction "VIN_2") (pintype "power_in"))
    )
    (net (code "17") (name "Net-(U2-VSW)") (class "Default")
      (node (ref "C9") (pin "1") (pinfunction "1_1") (pintype "passive"))
      (node (ref "J2") (pin "C") (pinfunction "C_C") (pintype "passive"))
      (node (ref "L2") (pin "1") (pinfunction "1_1") (pintype "passive"))
      (node (ref "U2") (pin "1") (pinfunction "VSW_1") (pintype "power_in"))
    )
    (net (code "18") (name "Net-(U3-CB)") (class "Default")
      (node (ref "C11") (pin "2") (pinfunction "2_2") (pintype "passive"))
      (node (ref "U3") (pin "3") (pinfunction "CB_3") (pintype "passive"))
    )
    (net (code "19") (name "Net-(U3-FB)") (class "Default")
      (node (ref "R5") (pin "1") (pinfunction "1_1") (pintype "passive"))
      (node (ref "R6") (pin "1") (pinfunction "1_1") (pintype "passive"))
      (node (ref "U3") (pin "6") (pinfunction "FB_6") (pintype "input"))
    )
    (net (code "20") (name "Net-(U3-VIN)") (class "Default")
      (node (ref "C5") (pin "2") (pinfunction "2_2") (pintype "passive"))
      (node (ref "C7") (pin "2") (pinfunction "2_2") (pintype "passive"))
      (node (ref "SW3") (pin "2") (pinfunction "2_2") (pintype "passive"))
      (node (ref "U3") (pin "2") (pinfunction "VIN_2") (pintype "power_in"))
    )
    (net (code "21") (name "Net-(U3-VSW)") (class "Default")
      (node (ref "C11") (pin "1") (pinfunction "1_1") (pintype "passive"))
      (node (ref "J3") (pin "C") (pinfunction "C_C") (pintype "passive"))
      (node (ref "L3") (pin "1") (pinfunction "1_1") (pintype "passive"))
      (node (ref "U3") (pin "1") (pinfunction "VSW_1") (pintype "power_in"))
    )
    (net (code "22") (name "unconnected-(U1-NC-Pad5)") (class "Default")
      (node (ref "U1") (pin "5") (pinfunction "NC_5") (pintype "passive"))
    )
    (net (code "23") (name "unconnected-(U1-ON{slash}~{OFF}-Pad7)") (class "Default")
      (node (ref "U1") (pin "7") (pinfunction "ON/~{OFF}_7") (pintype "input"))
    )
    (net (code "24") (name "unconnected-(U2-NC-Pad5)") (class "Default")
      (node (ref "U2") (pin "5") (pinfunction "NC_5") (pintype "passive"))
    )
    (net (code "25") (name "unconnected-(U2-ON{slash}~{OFF}-Pad7)") (class "Default")
      (node (ref "U2") (pin "7") (pinfunction "ON/~{OFF}_7") (pintype "input"))
    )
    (net (code "26") (name "unconnected-(U3-NC-Pad5)") (class "Default")
      (node (ref "U3") (pin "5") (pinfunction "NC_5") (pintype "passive"))
    )
    (net (code "27") (name "unconnected-(U3-ON{slash}~{OFF}-Pad7)") (class "Default")
      (node (ref "U3") (pin "7") (pinfunction "ON/~{OFF}_7") (pintype "input"))
    )
  )
)
